# secondary_18.net
KiCad netlist of a schematic drawn in EAGLE
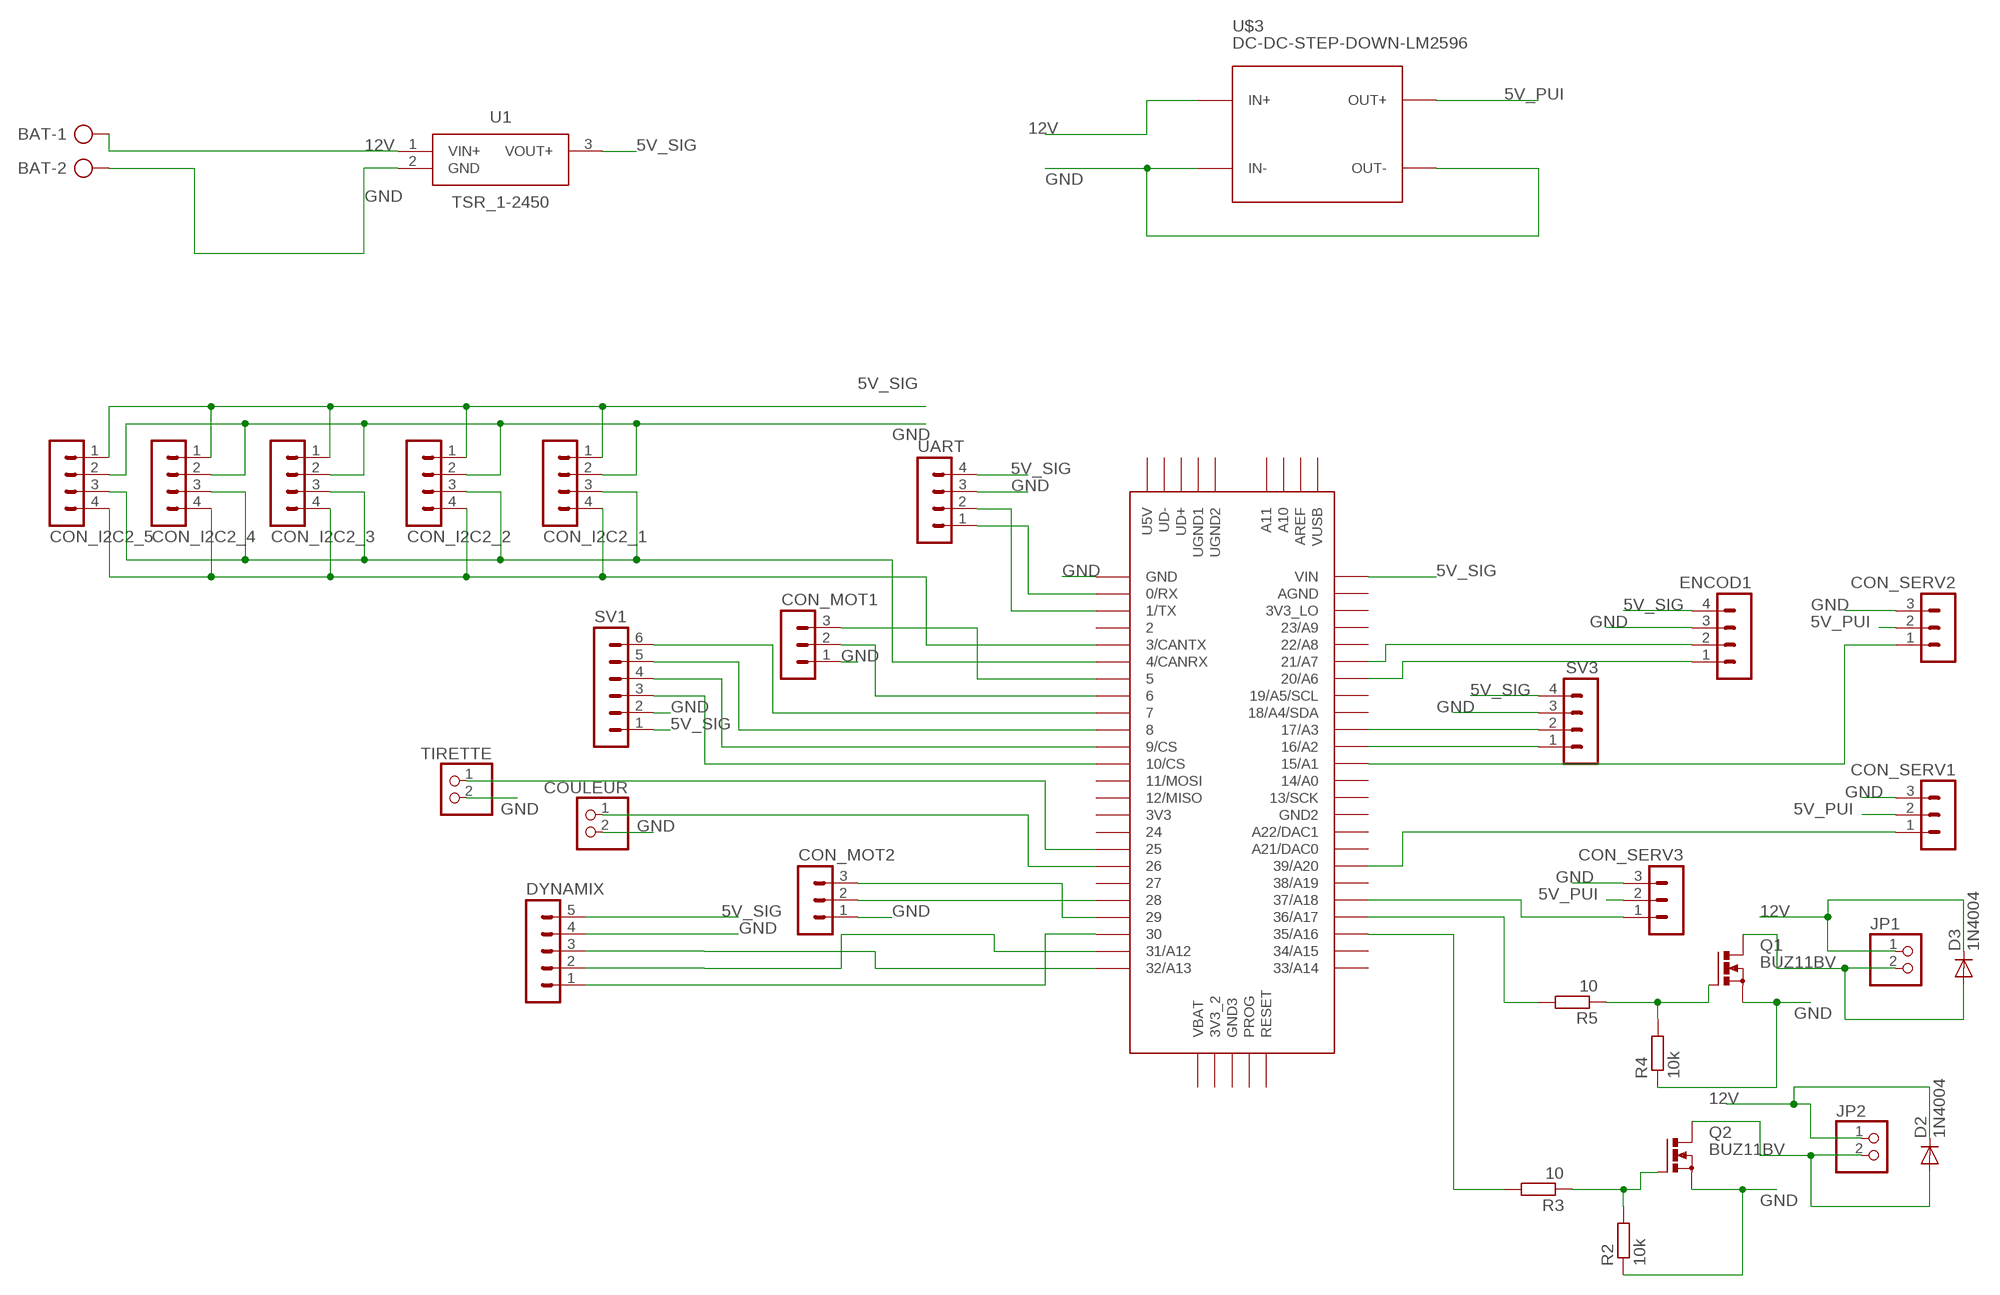
[diagram p0: schematic, sheet 1]

(export (version "E")
  (design (tool "Eeschema 10.0.6"))
  (components
    (comp (ref "BAT")
      (value "AK300/2")
      (footprint "eagle-import:AK300_2")
      (libsource (lib "eagle-import") (part "AK300/2"))
    )
    (comp (ref "CON_I2C2_1")
      (value "MA04-1")
      (footprint "eagle-import:MA04-1")
      (libsource (lib "eagle-import") (part "MA04-1"))
    )
    (comp (ref "CON_I2C2_2")
      (value "MA04-1")
      (footprint "eagle-import:MA04-1")
      (libsource (lib "eagle-import") (part "MA04-1"))
    )
    (comp (ref "CON_I2C2_3")
      (value "MA04-1")
      (footprint "eagle-import:MA04-1")
      (libsource (lib "eagle-import") (part "MA04-1"))
    )
    (comp (ref "CON_I2C2_4")
      (value "MA04-1")
      (footprint "eagle-import:MA04-1")
      (libsource (lib "eagle-import") (part "MA04-1"))
    )
    (comp (ref "CON_I2C2_5")
      (value "MA04-1")
      (footprint "eagle-import:MA04-1")
      (libsource (lib "eagle-import") (part "MA04-1"))
    )
    (comp (ref "CON_MOT1")
      (value "MA03-1")
      (footprint "eagle-import:MA03-1")
      (libsource (lib "eagle-import") (part "MA03-1"))
    )
    (comp (ref "CON_MOT2")
      (value "MA03-1")
      (footprint "eagle-import:MA03-1")
      (libsource (lib "eagle-import") (part "MA03-1"))
    )
    (comp (ref "CON_SERV1")
      (value "MA03-1")
      (footprint "eagle-import:MA03-1")
      (libsource (lib "eagle-import") (part "MA03-1"))
    )
    (comp (ref "CON_SERV2")
      (value "MA03-1")
      (footprint "eagle-import:MA03-1")
      (libsource (lib "eagle-import") (part "MA03-1"))
    )
    (comp (ref "CON_SERV3")
      (value "MA03-1")
      (footprint "eagle-import:MA03-1")
      (libsource (lib "eagle-import") (part "MA03-1"))
    )
    (comp (ref "COULEUR")
      (value "PINHD-1X2")
      (footprint "eagle-import:1X02")
      (libsource (lib "eagle-import") (part "PINHD-1X2"))
    )
    (comp (ref "D2")
      (value "1N4004")
      (footprint "eagle-import:DO41-10")
      (libsource (lib "eagle-import") (part "1N4004"))
    )
    (comp (ref "D3")
      (value "1N4004")
      (footprint "eagle-import:DO41-10")
      (libsource (lib "eagle-import") (part "1N4004"))
    )
    (comp (ref "DYNAMIX")
      (value "MA05-1")
      (footprint "eagle-import:MA05-1")
      (libsource (lib "eagle-import") (part "MA05-1"))
    )
    (comp (ref "ENCOD1")
      (value "MA04-1")
      (footprint "eagle-import:MA04-1")
      (libsource (lib "eagle-import") (part "MA04-1"))
    )
    (comp (ref "JP1")
      (value "PINHD-1X2")
      (footprint "eagle-import:1X02")
      (libsource (lib "eagle-import") (part "PINHD-1X2"))
    )
    (comp (ref "JP2")
      (value "PINHD-1X2")
      (footprint "eagle-import:1X02")
      (libsource (lib "eagle-import") (part "PINHD-1X2"))
    )
    (comp (ref "Q1")
      (value "BUZ11BV")
      (footprint "eagle-import:TO220BV")
      (libsource (lib "eagle-import") (part "BUZ11BV"))
    )
    (comp (ref "Q2")
      (value "BUZ11BV")
      (footprint "eagle-import:TO220BV")
      (libsource (lib "eagle-import") (part "BUZ11BV"))
    )
    (comp (ref "R2")
      (value "10k")
      (footprint "eagle-import:0204_7")
      (libsource (lib "eagle-import") (part "R-EU_0204/7"))
    )
    (comp (ref "R3")
      (value "10")
      (footprint "eagle-import:0204_7")
      (libsource (lib "eagle-import") (part "R-EU_0204/7"))
    )
    (comp (ref "R4")
      (value "10k")
      (footprint "eagle-import:0204_7")
      (libsource (lib "eagle-import") (part "R-EU_0204/7"))
    )
    (comp (ref "R5")
      (value "10")
      (footprint "eagle-import:0204_7")
      (libsource (lib "eagle-import") (part "R-EU_0204/7"))
    )
    (comp (ref "SV1")
      (value "MA06-1")
      (footprint "eagle-import:MA06-1")
      (libsource (lib "eagle-import") (part "MA06-1"))
    )
    (comp (ref "SV3")
      (value "MA04-1")
      (footprint "eagle-import:MA04-1")
      (libsource (lib "eagle-import") (part "MA04-1"))
    )
    (comp (ref "TIRETTE")
      (value "PINHD-1X2")
      (footprint "eagle-import:1X02")
      (libsource (lib "eagle-import") (part "PINHD-1X2"))
    )
    (comp (ref "U$1")
      (value "TEENSY_3.5/3.6")
      (footprint "eagle-import:TEENSY_3.5_3.6")
      (libsource (lib "eagle-import") (part "TEENSY_3.5/3.6"))
    )
    (comp (ref "U$3")
      (value "DC-DC-STEP-DOWN-LM2596")
      (footprint "eagle-import:DC-DC-STEP-DOWN-LM2596")
      (libsource (lib "eagle-import") (part "DC-DC-STEP-DOWN-LM2596"))
    )
    (comp (ref "U1")
      (value "TSR_1-2450")
      (footprint "eagle-import:TSR-1-24120")
      (fields
        (field (name "MANUFACTURER_PART_NUMBER") "TSR 1-2450")
        (field (name "RS_PART_NUMBER") "6664379P")
      )
      (libsource (lib "eagle-import") (part "TSR_1-2450"))
    )
    (comp (ref "UART")
      (value "MA04-1")
      (footprint "eagle-import:MA04-1")
      (libsource (lib "eagle-import") (part "MA04-1"))
    )
  )
  (nets
    (net (code "1") (name "/5V_PUI") (class "Default")
      (node (ref "CON_SERV1") (pin "2") (pinfunction "2_2") (pintype "passive"))
      (node (ref "CON_SERV2") (pin "2") (pinfunction "2_2") (pintype "passive"))
      (node (ref "CON_SERV3") (pin "2") (pinfunction "2_2") (pintype "passive"))
      (node (ref "U$3") (pin "OUT+") (pinfunction "OUT+_OUT+") (pintype "bidirectional"))
    )
    (net (code "2") (name "/5V_SIG") (class "Default")
      (node (ref "CON_I2C2_1") (pin "1") (pinfunction "1_1") (pintype "passive"))
      (node (ref "CON_I2C2_2") (pin "1") (pinfunction "1_1") (pintype "passive"))
      (node (ref "CON_I2C2_3") (pin "1") (pinfunction "1_1") (pintype "passive"))
      (node (ref "CON_I2C2_4") (pin "1") (pinfunction "1_1") (pintype "passive"))
      (node (ref "CON_I2C2_5") (pin "1") (pinfunction "1_1") (pintype "passive"))
      (node (ref "DYNAMIX") (pin "5") (pinfunction "5_5") (pintype "passive"))
      (node (ref "ENCOD1") (pin "4") (pinfunction "4_4") (pintype "passive"))
      (node (ref "SV1") (pin "1") (pinfunction "1_1") (pintype "passive"))
      (node (ref "SV3") (pin "4") (pinfunction "4_4") (pintype "passive"))
      (node (ref "U$1") (pin "VIN") (pinfunction "VIN_VIN") (pintype "bidirectional"))
      (node (ref "U1") (pin "3") (pinfunction "VOUT+_3") (pintype "input"))
      (node (ref "UART") (pin "4") (pinfunction "4_4") (pintype "passive"))
    )
    (net (code "3") (name "/12V") (class "Default")
      (node (ref "BAT") (pin "1") (pinfunction "KL_1") (pintype "passive"))
      (node (ref "D2") (pin "C") (pinfunction "C_C") (pintype "passive"))
      (node (ref "D3") (pin "C") (pinfunction "C_C") (pintype "passive"))
      (node (ref "JP1") (pin "1") (pinfunction "1_1") (pintype "passive"))
      (node (ref "JP2") (pin "1") (pinfunction "1_1") (pintype "passive"))
      (node (ref "U$3") (pin "IN+") (pinfunction "IN+_IN+") (pintype "bidirectional"))
      (node (ref "U1") (pin "1") (pinfunction "VIN+_1") (pintype "input"))
    )
    (net (code "4") (name "/GND") (class "Default")
      (node (ref "BAT") (pin "2") (pinfunction "KL_2") (pintype "passive"))
      (node (ref "CON_I2C2_1") (pin "2") (pinfunction "2_2") (pintype "passive"))
      (node (ref "CON_I2C2_2") (pin "2") (pinfunction "2_2") (pintype "passive"))
      (node (ref "CON_I2C2_3") (pin "2") (pinfunction "2_2") (pintype "passive"))
      (node (ref "CON_I2C2_4") (pin "2") (pinfunction "2_2") (pintype "passive"))
      (node (ref "CON_I2C2_5") (pin "2") (pinfunction "2_2") (pintype "passive"))
      (node (ref "CON_MOT1") (pin "1") (pinfunction "1_1") (pintype "passive"))
      (node (ref "CON_MOT2") (pin "1") (pinfunction "1_1") (pintype "passive"))
      (node (ref "CON_SERV1") (pin "3") (pinfunction "3_3") (pintype "passive"))
      (node (ref "CON_SERV2") (pin "3") (pinfunction "3_3") (pintype "passive"))
      (node (ref "CON_SERV3") (pin "3") (pinfunction "3_3") (pintype "passive"))
      (node (ref "COULEUR") (pin "2") (pinfunction "2_2") (pintype "passive"))
      (node (ref "DYNAMIX") (pin "4") (pinfunction "4_4") (pintype "passive"))
      (node (ref "ENCOD1") (pin "3") (pinfunction "3_3") (pintype "passive"))
      (node (ref "Q1") (pin "S") (pinfunction "S_S") (pintype "passive"))
      (node (ref "Q2") (pin "S") (pinfunction "S_S") (pintype "passive"))
      (node (ref "R2") (pin "1") (pinfunction "1_1") (pintype "passive"))
      (node (ref "R4") (pin "1") (pinfunction "1_1") (pintype "passive"))
      (node (ref "SV1") (pin "2") (pinfunction "2_2") (pintype "passive"))
      (node (ref "SV3") (pin "3") (pinfunction "3_3") (pintype "passive"))
      (node (ref "TIRETTE") (pin "2") (pinfunction "2_2") (pintype "passive"))
      (node (ref "U$1") (pin "GND") (pinfunction "GND_GND") (pintype "bidirectional"))
      (node (ref "U$3") (pin "IN-") (pinfunction "IN-_IN-") (pintype "bidirectional"))
      (node (ref "U$3") (pin "OUT-") (pinfunction "OUT-_OUT-") (pintype "bidirectional"))
      (node (ref "U1") (pin "2") (pinfunction "GND_2") (pintype "power_in"))
      (node (ref "UART") (pin "3") (pinfunction "3_3") (pintype "passive"))
    )
    (net (code "5") (name "Net-(CON_I2C2_1-Pad3)") (class "Default")
      (node (ref "CON_I2C2_1") (pin "3") (pinfunction "3_3") (pintype "passive"))
      (node (ref "CON_I2C2_2") (pin "3") (pinfunction "3_3") (pintype "passive"))
      (node (ref "CON_I2C2_3") (pin "3") (pinfunction "3_3") (pintype "passive"))
      (node (ref "CON_I2C2_4") (pin "3") (pinfunction "3_3") (pintype "passive"))
      (node (ref "CON_I2C2_5") (pin "3") (pinfunction "3_3") (pintype "passive"))
      (node (ref "U$1") (pin "4/CANRX") (pinfunction "4/CANRX_4/CANRX") (pintype "bidirectional"))
    )
    (net (code "6") (name "Net-(CON_I2C2_1-Pad4)") (class "Default")
      (node (ref "CON_I2C2_1") (pin "4") (pinfunction "4_4") (pintype "passive"))
      (node (ref "CON_I2C2_2") (pin "4") (pinfunction "4_4") (pintype "passive"))
      (node (ref "CON_I2C2_3") (pin "4") (pinfunction "4_4") (pintype "passive"))
      (node (ref "CON_I2C2_4") (pin "4") (pinfunction "4_4") (pintype "passive"))
      (node (ref "CON_I2C2_5") (pin "4") (pinfunction "4_4") (pintype "passive"))
      (node (ref "U$1") (pin "3/CANTX") (pinfunction "3/CANTX_3/CANTX") (pintype "bidirectional"))
    )
    (net (code "7") (name "Net-(CON_MOT1-Pad2)") (class "Default")
      (node (ref "CON_MOT1") (pin "2") (pinfunction "2_2") (pintype "passive"))
      (node (ref "U$1") (pin "6") (pinfunction "6_6") (pintype "bidirectional"))
    )
    (net (code "8") (name "Net-(CON_MOT1-Pad3)") (class "Default")
      (node (ref "CON_MOT1") (pin "3") (pinfunction "3_3") (pintype "passive"))
      (node (ref "U$1") (pin "5") (pinfunction "5_5") (pintype "bidirectional"))
    )
    (net (code "9") (name "Net-(CON_MOT2-Pad2)") (class "Default")
      (node (ref "CON_MOT2") (pin "2") (pinfunction "2_2") (pintype "passive"))
      (node (ref "U$1") (pin "28") (pinfunction "28_28") (pintype "bidirectional"))
    )
    (net (code "10") (name "Net-(CON_MOT2-Pad3)") (class "Default")
      (node (ref "CON_MOT2") (pin "3") (pinfunction "3_3") (pintype "passive"))
      (node (ref "U$1") (pin "29") (pinfunction "29_29") (pintype "bidirectional"))
    )
    (net (code "11") (name "Net-(CON_SERV1-Pad1)") (class "Default")
      (node (ref "CON_SERV1") (pin "1") (pinfunction "1_1") (pintype "passive"))
      (node (ref "U$1") (pin "39/A20") (pinfunction "39/A20_39/A20") (pintype "bidirectional"))
    )
    (net (code "12") (name "Net-(CON_SERV2-Pad1)") (class "Default")
      (node (ref "CON_SERV2") (pin "1") (pinfunction "1_1") (pintype "passive"))
      (node (ref "U$1") (pin "15/A1") (pinfunction "15/A1_15/A1") (pintype "bidirectional"))
    )
    (net (code "13") (name "Net-(CON_SERV3-Pad1)") (class "Default")
      (node (ref "CON_SERV3") (pin "1") (pinfunction "1_1") (pintype "passive"))
      (node (ref "U$1") (pin "37/A18") (pinfunction "37/A18_37/A18") (pintype "bidirectional"))
    )
    (net (code "14") (name "Net-(COULEUR-Pad1)") (class "Default")
      (node (ref "COULEUR") (pin "1") (pinfunction "1_1") (pintype "passive"))
      (node (ref "U$1") (pin "26") (pinfunction "26_26") (pintype "bidirectional"))
    )
    (net (code "15") (name "Net-(D2-PadA)") (class "Default")
      (node (ref "D2") (pin "A") (pinfunction "A_A") (pintype "passive"))
      (node (ref "JP2") (pin "2") (pinfunction "2_2") (pintype "passive"))
      (node (ref "Q2") (pin "D") (pinfunction "D_D") (pintype "passive"))
    )
    (net (code "16") (name "Net-(D3-PadA)") (class "Default")
      (node (ref "D3") (pin "A") (pinfunction "A_A") (pintype "passive"))
      (node (ref "JP1") (pin "2") (pinfunction "2_2") (pintype "passive"))
      (node (ref "Q1") (pin "D") (pinfunction "D_D") (pintype "passive"))
    )
    (net (code "17") (name "Net-(DYNAMIX-Pad1)") (class "Default")
      (node (ref "DYNAMIX") (pin "1") (pinfunction "1_1") (pintype "passive"))
      (node (ref "U$1") (pin "30") (pinfunction "30_30") (pintype "bidirectional"))
    )
    (net (code "18") (name "Net-(DYNAMIX-Pad2)") (class "Default")
      (node (ref "DYNAMIX") (pin "2") (pinfunction "2_2") (pintype "passive"))
      (node (ref "U$1") (pin "31/A12") (pinfunction "31/A12_31/A12") (pintype "bidirectional"))
    )
    (net (code "19") (name "Net-(DYNAMIX-Pad3)") (class "Default")
      (node (ref "DYNAMIX") (pin "3") (pinfunction "3_3") (pintype "passive"))
      (node (ref "U$1") (pin "32/A13") (pinfunction "32/A13_32/A13") (pintype "bidirectional"))
    )
    (net (code "20") (name "Net-(ENCOD1-Pad1)") (class "Default")
      (node (ref "ENCOD1") (pin "1") (pinfunction "1_1") (pintype "passive"))
      (node (ref "U$1") (pin "20/A6") (pinfunction "20/A6_20/A6") (pintype "bidirectional"))
    )
    (net (code "21") (name "Net-(ENCOD1-Pad2)") (class "Default")
      (node (ref "ENCOD1") (pin "2") (pinfunction "2_2") (pintype "passive"))
      (node (ref "U$1") (pin "21/A7") (pinfunction "21/A7_21/A7") (pintype "bidirectional"))
    )
    (net (code "22") (name "Net-(Q1-PadG)") (class "Default")
      (node (ref "Q1") (pin "G") (pinfunction "G_G") (pintype "passive"))
      (node (ref "R4") (pin "2") (pinfunction "2_2") (pintype "passive"))
      (node (ref "R5") (pin "1") (pinfunction "1_1") (pintype "passive"))
    )
    (net (code "23") (name "Net-(Q2-PadG)") (class "Default")
      (node (ref "Q2") (pin "G") (pinfunction "G_G") (pintype "passive"))
      (node (ref "R2") (pin "2") (pinfunction "2_2") (pintype "passive"))
      (node (ref "R3") (pin "1") (pinfunction "1_1") (pintype "passive"))
    )
    (net (code "24") (name "Net-(R3-Pad2)") (class "Default")
      (node (ref "R3") (pin "2") (pinfunction "2_2") (pintype "passive"))
      (node (ref "U$1") (pin "35/A16") (pinfunction "35/A16_35/A16") (pintype "bidirectional"))
    )
    (net (code "25") (name "Net-(R5-Pad2)") (class "Default")
      (node (ref "R5") (pin "2") (pinfunction "2_2") (pintype "passive"))
      (node (ref "U$1") (pin "36/A17") (pinfunction "36/A17_36/A17") (pintype "bidirectional"))
    )
    (net (code "26") (name "Net-(SV1-Pad3)") (class "Default")
      (node (ref "SV1") (pin "3") (pinfunction "3_3") (pintype "passive"))
      (node (ref "U$1") (pin "10/CS") (pinfunction "10/CS_10/CS") (pintype "bidirectional"))
    )
    (net (code "27") (name "Net-(SV1-Pad4)") (class "Default")
      (node (ref "SV1") (pin "4") (pinfunction "4_4") (pintype "passive"))
      (node (ref "U$1") (pin "9/CS") (pinfunction "9/CS_9/CS") (pintype "bidirectional"))
    )
    (net (code "28") (name "Net-(SV1-Pad5)") (class "Default")
      (node (ref "SV1") (pin "5") (pinfunction "5_5") (pintype "passive"))
      (node (ref "U$1") (pin "8") (pinfunction "8_8") (pintype "bidirectional"))
    )
    (net (code "29") (name "Net-(SV1-Pad6)") (class "Default")
      (node (ref "SV1") (pin "6") (pinfunction "6_6") (pintype "passive"))
      (node (ref "U$1") (pin "7") (pinfunction "7_7") (pintype "bidirectional"))
    )
    (net (code "30") (name "Net-(SV3-Pad1)") (class "Default")
      (node (ref "SV3") (pin "1") (pinfunction "1_1") (pintype "passive"))
      (node (ref "U$1") (pin "16/A2") (pinfunction "16/A2_16/A2") (pintype "bidirectional"))
    )
    (net (code "31") (name "Net-(SV3-Pad2)") (class "Default")
      (node (ref "SV3") (pin "2") (pinfunction "2_2") (pintype "passive"))
      (node (ref "U$1") (pin "17/A3") (pinfunction "17/A3_17/A3") (pintype "bidirectional"))
    )
    (net (code "32") (name "Net-(TIRETTE-Pad1)") (class "Default")
      (node (ref "TIRETTE") (pin "1") (pinfunction "1_1") (pintype "passive"))
      (node (ref "U$1") (pin "25") (pinfunction "25_25") (pintype "bidirectional"))
    )
    (net (code "33") (name "Net-(U$1-Pad0{slash}RX)") (class "Default")
      (node (ref "U$1") (pin "0/RX") (pinfunction "0/RX_0/RX") (pintype "bidirectional"))
      (node (ref "UART") (pin "1") (pinfunction "1_1") (pintype "passive"))
    )
    (net (code "34") (name "Net-(U$1-Pad1{slash}TX)") (class "Default")
      (node (ref "U$1") (pin "1/TX") (pinfunction "1/TX_1/TX") (pintype "bidirectional"))
      (node (ref "UART") (pin "2") (pinfunction "2_2") (pintype "passive"))
    )
    (net (code "35") (name "unconnected-(U$1-A21{slash}DAC0-Pad21{slash}DAC0)") (class "Default")
      (node (ref "U$1") (pin "21/DAC0") (pinfunction "A21/DAC0_21/DAC0") (pintype "bidirectional"))
    )
    (net (code "36") (name "unconnected-(U$1-Pad2)") (class "Default")
      (node (ref "U$1") (pin "2") (pinfunction "2_2") (pintype "bidirectional"))
    )
    (net (code "37") (name "unconnected-(U$1-Pad3V3)") (class "Default")
      (node (ref "U$1") (pin "3V3") (pinfunction "3V3_3V3") (pintype "bidirectional"))
    )
    (net (code "38") (name "unconnected-(U$1-Pad3V3_2)") (class "Default")
      (node (ref "U$1") (pin "3V3_2") (pinfunction "3V3_2_3V3_2") (pintype "bidirectional"))
    )
    (net (code "39") (name "unconnected-(U$1-Pad3V3_LO)") (class "Default")
      (node (ref "U$1") (pin "3V3_LO") (pinfunction "3V3_LO_3V3_LO") (pintype "bidirectional"))
    )
    (net (code "40") (name "unconnected-(U$1-Pad11{slash}MOSI)") (class "Default")
      (node (ref "U$1") (pin "11/MOSI") (pinfunction "11/MOSI_11/MOSI") (pintype "bidirectional"))
    )
    (net (code "41") (name "unconnected-(U$1-Pad12{slash}MISO)") (class "Default")
      (node (ref "U$1") (pin "12/MISO") (pinfunction "12/MISO_12/MISO") (pintype "bidirectional"))
    )
    (net (code "42") (name "unconnected-(U$1-Pad13{slash}SCK)") (class "Default")
      (node (ref "U$1") (pin "13/SCK") (pinfunction "13/SCK_13/SCK") (pintype "bidirectional"))
    )
    (net (code "43") (name "unconnected-(U$1-Pad14{slash}A0)") (class "Default")
      (node (ref "U$1") (pin "14/A0") (pinfunction "14/A0_14/A0") (pintype "bidirectional"))
    )
    (net (code "44") (name "unconnected-(U$1-Pad18{slash}A4{slash}SDA)") (class "Default")
      (node (ref "U$1") (pin "18/A4/SDA") (pinfunction "18/A4/SDA_18/A4/SDA") (pintype "bidirectional"))
    )
    (net (code "45") (name "unconnected-(U$1-Pad19{slash}A5{slash}SCL)") (class "Default")
      (node (ref "U$1") (pin "19/A5/SCL") (pinfunction "19/A5/SCL_19/A5/SCL") (pintype "bidirectional"))
    )
    (net (code "46") (name "unconnected-(U$1-Pad22{slash}A8)") (class "Default")
      (node (ref "U$1") (pin "22/A8") (pinfunction "22/A8_22/A8") (pintype "bidirectional"))
    )
    (net (code "47") (name "unconnected-(U$1-Pad23{slash}A9)") (class "Default")
      (node (ref "U$1") (pin "23/A9") (pinfunction "23/A9_23/A9") (pintype "bidirectional"))
    )
    (net (code "48") (name "unconnected-(U$1-Pad24)") (class "Default")
      (node (ref "U$1") (pin "24") (pinfunction "24_24") (pintype "bidirectional"))
    )
    (net (code "49") (name "unconnected-(U$1-Pad27)") (class "Default")
      (node (ref "U$1") (pin "27") (pinfunction "27_27") (pintype "bidirectional"))
    )
    (net (code "50") (name "unconnected-(U$1-Pad33{slash}A14)") (class "Default")
      (node (ref "U$1") (pin "33/A14") (pinfunction "33/A14_33/A14") (pintype "bidirectional"))
    )
    (net (code "51") (name "unconnected-(U$1-Pad34{slash}A15)") (class "Default")
      (node (ref "U$1") (pin "34/A15") (pinfunction "34/A15_34/A15") (pintype "bidirectional"))
    )
    (net (code "52") (name "unconnected-(U$1-Pad38{slash}A19)") (class "Default")
      (node (ref "U$1") (pin "38/A19") (pinfunction "38/A19_38/A19") (pintype "bidirectional"))
    )
    (net (code "53") (name "unconnected-(U$1-PadA10)") (class "Default")
      (node (ref "U$1") (pin "A10") (pinfunction "A10_A10") (pintype "bidirectional"))
    )
    (net (code "54") (name "unconnected-(U$1-PadA11)") (class "Default")
      (node (ref "U$1") (pin "A11") (pinfunction "A11_A11") (pintype "bidirectional"))
    )
    (net (code "55") (name "unconnected-(U$1-PadA22{slash}DAC1)") (class "Default")
      (node (ref "U$1") (pin "A22/DAC1") (pinfunction "A22/DAC1_A22/DAC1") (pintype "bidirectional"))
    )
    (net (code "56") (name "unconnected-(U$1-PadAGND)") (class "Default")
      (node (ref "U$1") (pin "AGND") (pinfunction "AGND_AGND") (pintype "bidirectional"))
    )
    (net (code "57") (name "unconnected-(U$1-PadAREF)") (class "Default")
      (node (ref "U$1") (pin "AREF") (pinfunction "AREF_AREF") (pintype "bidirectional"))
    )
    (net (code "58") (name "unconnected-(U$1-PadGND2)") (class "Default")
      (node (ref "U$1") (pin "GND2") (pinfunction "GND2_GND2") (pintype "bidirectional"))
    )
    (net (code "59") (name "unconnected-(U$1-PadGND3)") (class "Default")
      (node (ref "U$1") (pin "GND3") (pinfunction "GND3_GND3") (pintype "bidirectional"))
    )
    (net (code "60") (name "unconnected-(U$1-PadPROG)") (class "Default")
      (node (ref "U$1") (pin "PROG") (pinfunction "PROG_PROG") (pintype "bidirectional"))
    )
    (net (code "61") (name "unconnected-(U$1-PadRESET)") (class "Default")
      (node (ref "U$1") (pin "RESET") (pinfunction "RESET_RESET") (pintype "bidirectional"))
    )
    (net (code "62") (name "unconnected-(U$1-PadU5V)") (class "Default")
      (node (ref "U$1") (pin "U5V") (pinfunction "U5V_U5V") (pintype "bidirectional"))
    )
    (net (code "63") (name "unconnected-(U$1-PadUD+)") (class "Default")
      (node (ref "U$1") (pin "UD+") (pinfunction "UD+_UD+") (pintype "bidirectional"))
    )
    (net (code "64") (name "unconnected-(U$1-PadUD-)") (class "Default")
      (node (ref "U$1") (pin "UD-") (pinfunction "UD-_UD-") (pintype "bidirectional"))
    )
    (net (code "65") (name "unconnected-(U$1-PadUGND1)") (class "Default")
      (node (ref "U$1") (pin "UGND1") (pinfunction "UGND1_UGND1") (pintype "bidirectional"))
    )
    (net (code "66") (name "unconnected-(U$1-PadUGND2)") (class "Default")
      (node (ref "U$1") (pin "UGND2") (pinfunction "UGND2_UGND2") (pintype "bidirectional"))
    )
    (net (code "67") (name "unconnected-(U$1-PadVBAT)") (class "Default")
      (node (ref "U$1") (pin "VBAT") (pinfunction "VBAT_VBAT") (pintype "bidirectional"))
    )
    (net (code "68") (name "unconnected-(U$1-PadVUSB)") (class "Default")
      (node (ref "U$1") (pin "VUSB") (pinfunction "VUSB_VUSB") (pintype "bidirectional"))
    )
  )
)
